# RectifierPart.net
KiCad netlist of a schematic drawn in EAGLE
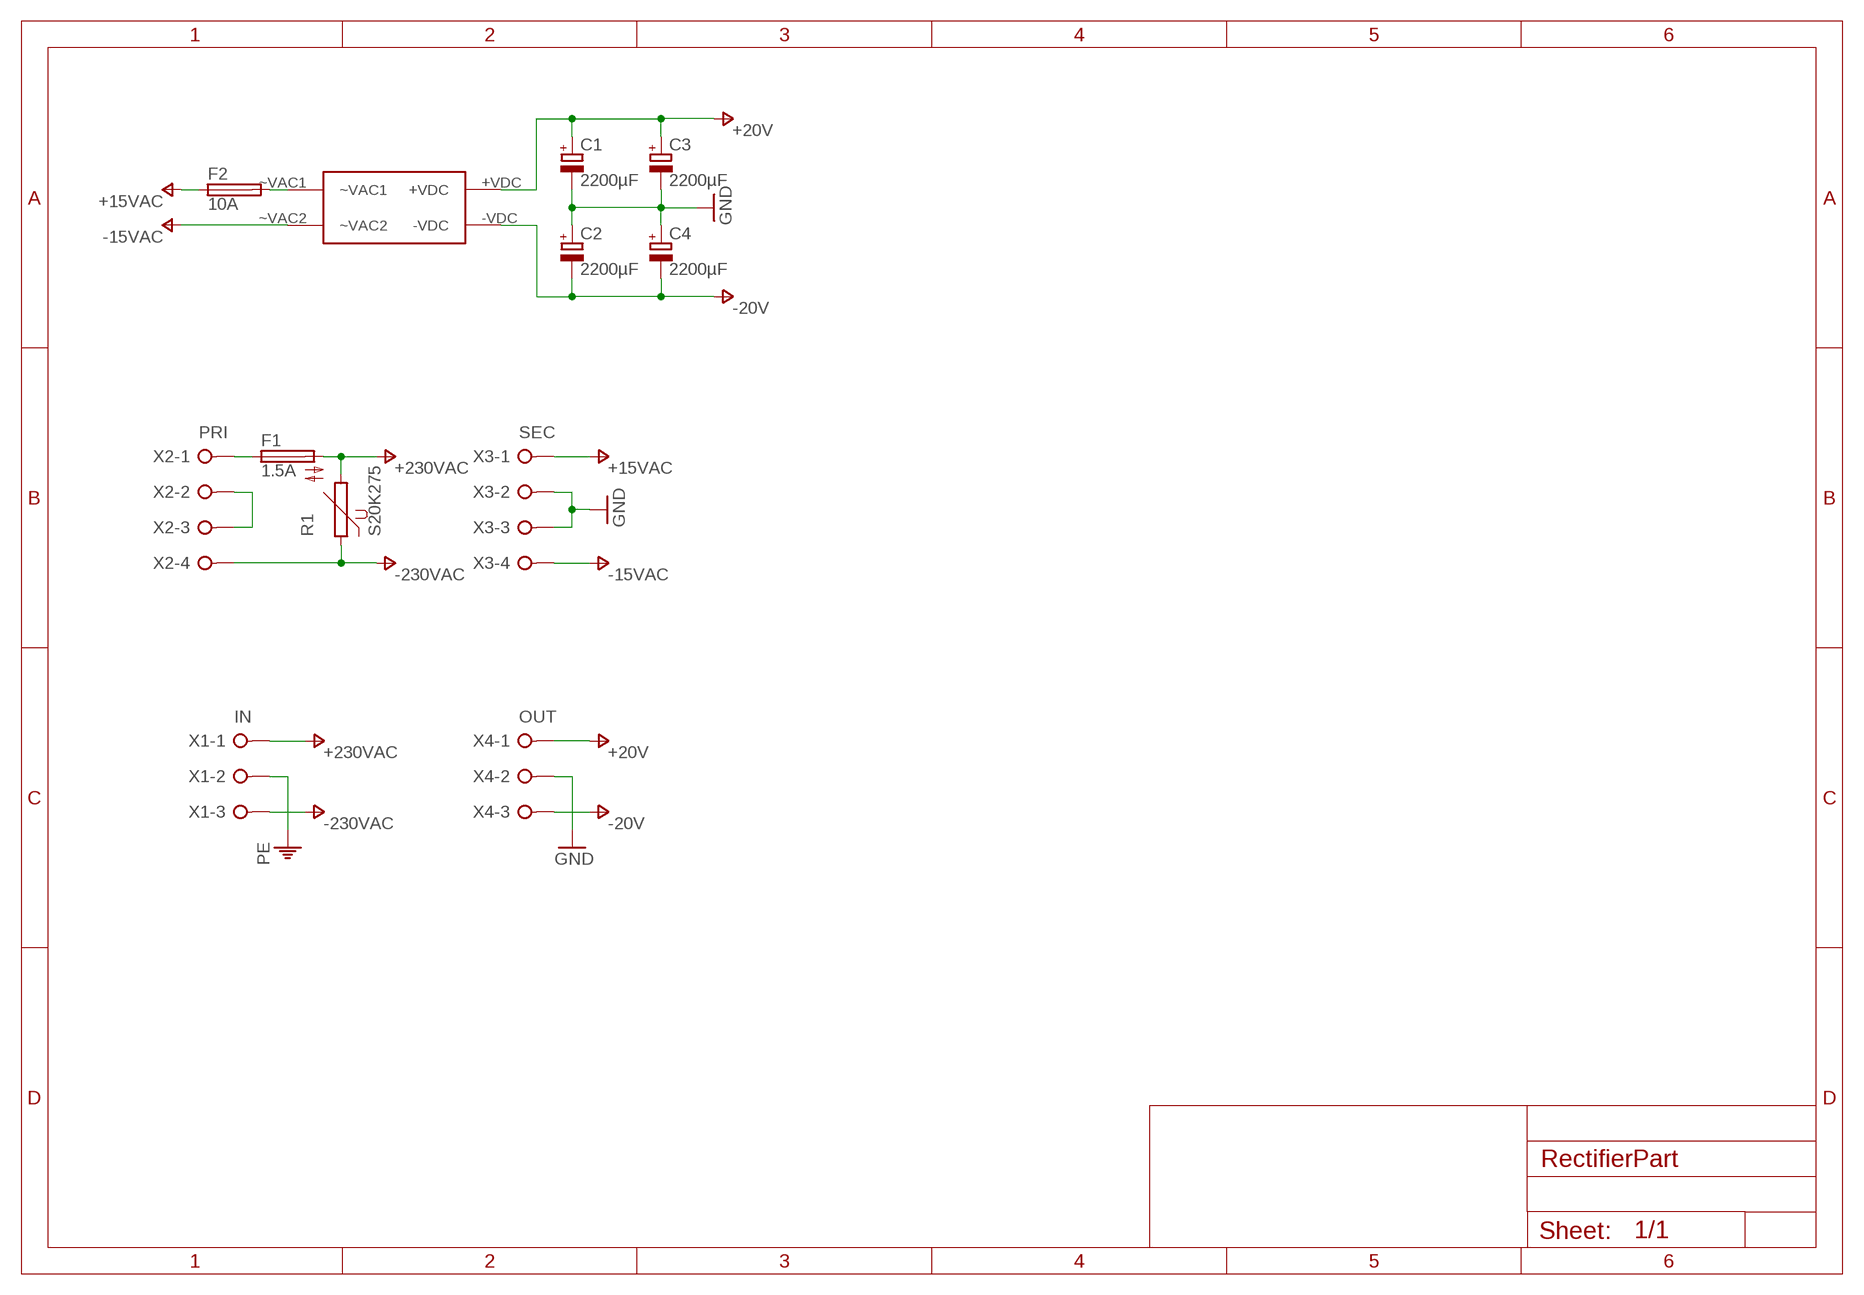
[diagram p0: schematic, sheet 1]

(export (version "E")
  (design (tool "Eeschema 10.0.6"))
  (components
    (comp (ref "C1")
      (value "2200µF")
      (footprint "eagle-import:E7,5-16")
      (libsource (lib "eagle-import") (part "CPOL-EUE7.5-16"))
    )
    (comp (ref "C2")
      (value "2200µF")
      (footprint "eagle-import:E7,5-16")
      (libsource (lib "eagle-import") (part "CPOL-EUE7.5-16"))
    )
    (comp (ref "C3")
      (value "2200µF")
      (footprint "eagle-import:E7,5-16")
      (libsource (lib "eagle-import") (part "CPOL-EUE7.5-16"))
    )
    (comp (ref "C4")
      (value "2200µF")
      (footprint "eagle-import:E7,5-16")
      (libsource (lib "eagle-import") (part "CPOL-EUE7.5-16"))
    )
    (comp (ref "F1")
      (value "1.5A")
      (footprint "eagle-import:SH22,5A")
      (fields (field (name "MPN") "0031.7701.11"))
      (libsource (lib "eagle-import") (part "SH22,5A"))
    )
    (comp (ref "F2")
      (value "10A")
      (footprint "eagle-import:SH22,5A")
      (fields (field (name "MPN") "0031.7701.11"))
      (libsource (lib "eagle-import") (part "SH22,5A"))
    )
    (comp (ref "R+1")
      (value "B40C5000-3300A")
      (footprint "eagle-import:B..C")
      (libsource (lib "eagle-import") (part "B40C5000-3300A"))
    )
    (comp (ref "R1")
      (value "S20K275")
      (footprint "eagle-import:S20K275")
      (libsource (lib "eagle-import") (part "S20K275"))
    )
    (comp (ref "X1")
      (value "IN")
      (footprint "eagle-import:W237-133")
      (libsource (lib "eagle-import") (part "W237-03P"))
    )
    (comp (ref "X2")
      (value "PRI")
      (footprint "eagle-import:W237-4P")
      (libsource (lib "eagle-import") (part "W237-04P"))
    )
    (comp (ref "X3")
      (value "SEC")
      (footprint "eagle-import:W237-4P")
      (libsource (lib "eagle-import") (part "W237-04P"))
    )
    (comp (ref "X4")
      (value "OUT")
      (footprint "eagle-import:W237-133")
      (libsource (lib "eagle-import") (part "W237-03P"))
    )
  )
  (nets
    (net (code "1") (name "+15VAC") (class "Default")
      (node (ref "F2") (pin "1") (pinfunction "1_1") (pintype "passive"))
      (node (ref "X3") (pin "1") (pinfunction "KL_1") (pintype "passive"))
    )
    (net (code "2") (name "+20V") (class "Default")
      (node (ref "C1") (pin "+") (pinfunction "+_+") (pintype "passive"))
      (node (ref "C3") (pin "+") (pinfunction "+_+") (pintype "passive"))
      (node (ref "R+1") (pin "+VDC") (pinfunction "+VDC_+VDC") (pintype "bidirectional"))
      (node (ref "X4") (pin "1") (pinfunction "KL_1") (pintype "passive"))
    )
    (net (code "3") (name "+230VAC") (class "Default")
      (node (ref "F1") (pin "2") (pinfunction "2_2") (pintype "passive"))
      (node (ref "R1") (pin "2") (pinfunction "2_2") (pintype "passive"))
      (node (ref "X1") (pin "1") (pinfunction "KL_1") (pintype "passive"))
    )
    (net (code "4") (name "-15VAC") (class "Default")
      (node (ref "R+1") (pin "~VAC2") (pinfunction "~{VAC2}_~VAC2") (pintype "bidirectional"))
      (node (ref "X3") (pin "4") (pinfunction "KL_4") (pintype "passive"))
    )
    (net (code "5") (name "-20V") (class "Default")
      (node (ref "C2") (pin "-") (pinfunction "-_-") (pintype "passive"))
      (node (ref "C4") (pin "-") (pinfunction "-_-") (pintype "passive"))
      (node (ref "R+1") (pin "-VDC") (pinfunction "-VDC_-VDC") (pintype "bidirectional"))
      (node (ref "X4") (pin "3") (pinfunction "KL_3") (pintype "passive"))
    )
    (net (code "6") (name "-230VAC") (class "Default")
      (node (ref "R1") (pin "1") (pinfunction "1_1") (pintype "passive"))
      (node (ref "X1") (pin "3") (pinfunction "KL_3") (pintype "passive"))
      (node (ref "X2") (pin "4") (pinfunction "KL_4") (pintype "passive"))
    )
    (net (code "7") (name "GND") (class "Default")
      (node (ref "C1") (pin "-") (pinfunction "-_-") (pintype "passive"))
      (node (ref "C2") (pin "+") (pinfunction "+_+") (pintype "passive"))
      (node (ref "C3") (pin "-") (pinfunction "-_-") (pintype "passive"))
      (node (ref "C4") (pin "+") (pinfunction "+_+") (pintype "passive"))
      (node (ref "X3") (pin "2") (pinfunction "KL_2") (pintype "passive"))
      (node (ref "X3") (pin "3") (pinfunction "KL_3") (pintype "passive"))
      (node (ref "X4") (pin "2") (pinfunction "KL_2") (pintype "passive"))
    )
    (net (code "8") (name "Net-(R+1-~{VAC1})") (class "Default")
      (node (ref "F2") (pin "2") (pinfunction "2_2") (pintype "passive"))
      (node (ref "R+1") (pin "~VAC1") (pinfunction "~{VAC1}_~VAC1") (pintype "bidirectional"))
    )
    (net (code "9") (name "Net-(X2A-KL)") (class "Default")
      (node (ref "F1") (pin "1") (pinfunction "1_1") (pintype "passive"))
      (node (ref "X2") (pin "1") (pinfunction "KL_1") (pintype "passive"))
    )
    (net (code "10") (name "Net-(X2B-KL)") (class "Default")
      (node (ref "X2") (pin "2") (pinfunction "KL_2") (pintype "passive"))
      (node (ref "X2") (pin "3") (pinfunction "KL_3") (pintype "passive"))
    )
    (net (code "11") (name "PE") (class "Default")
      (node (ref "X1") (pin "2") (pinfunction "KL_2") (pintype "passive"))
    )
  )
)
